# SCH_RGS-Turret_2023-06-20.net
KiCad netlist of a schematic drawn in EasyEDA
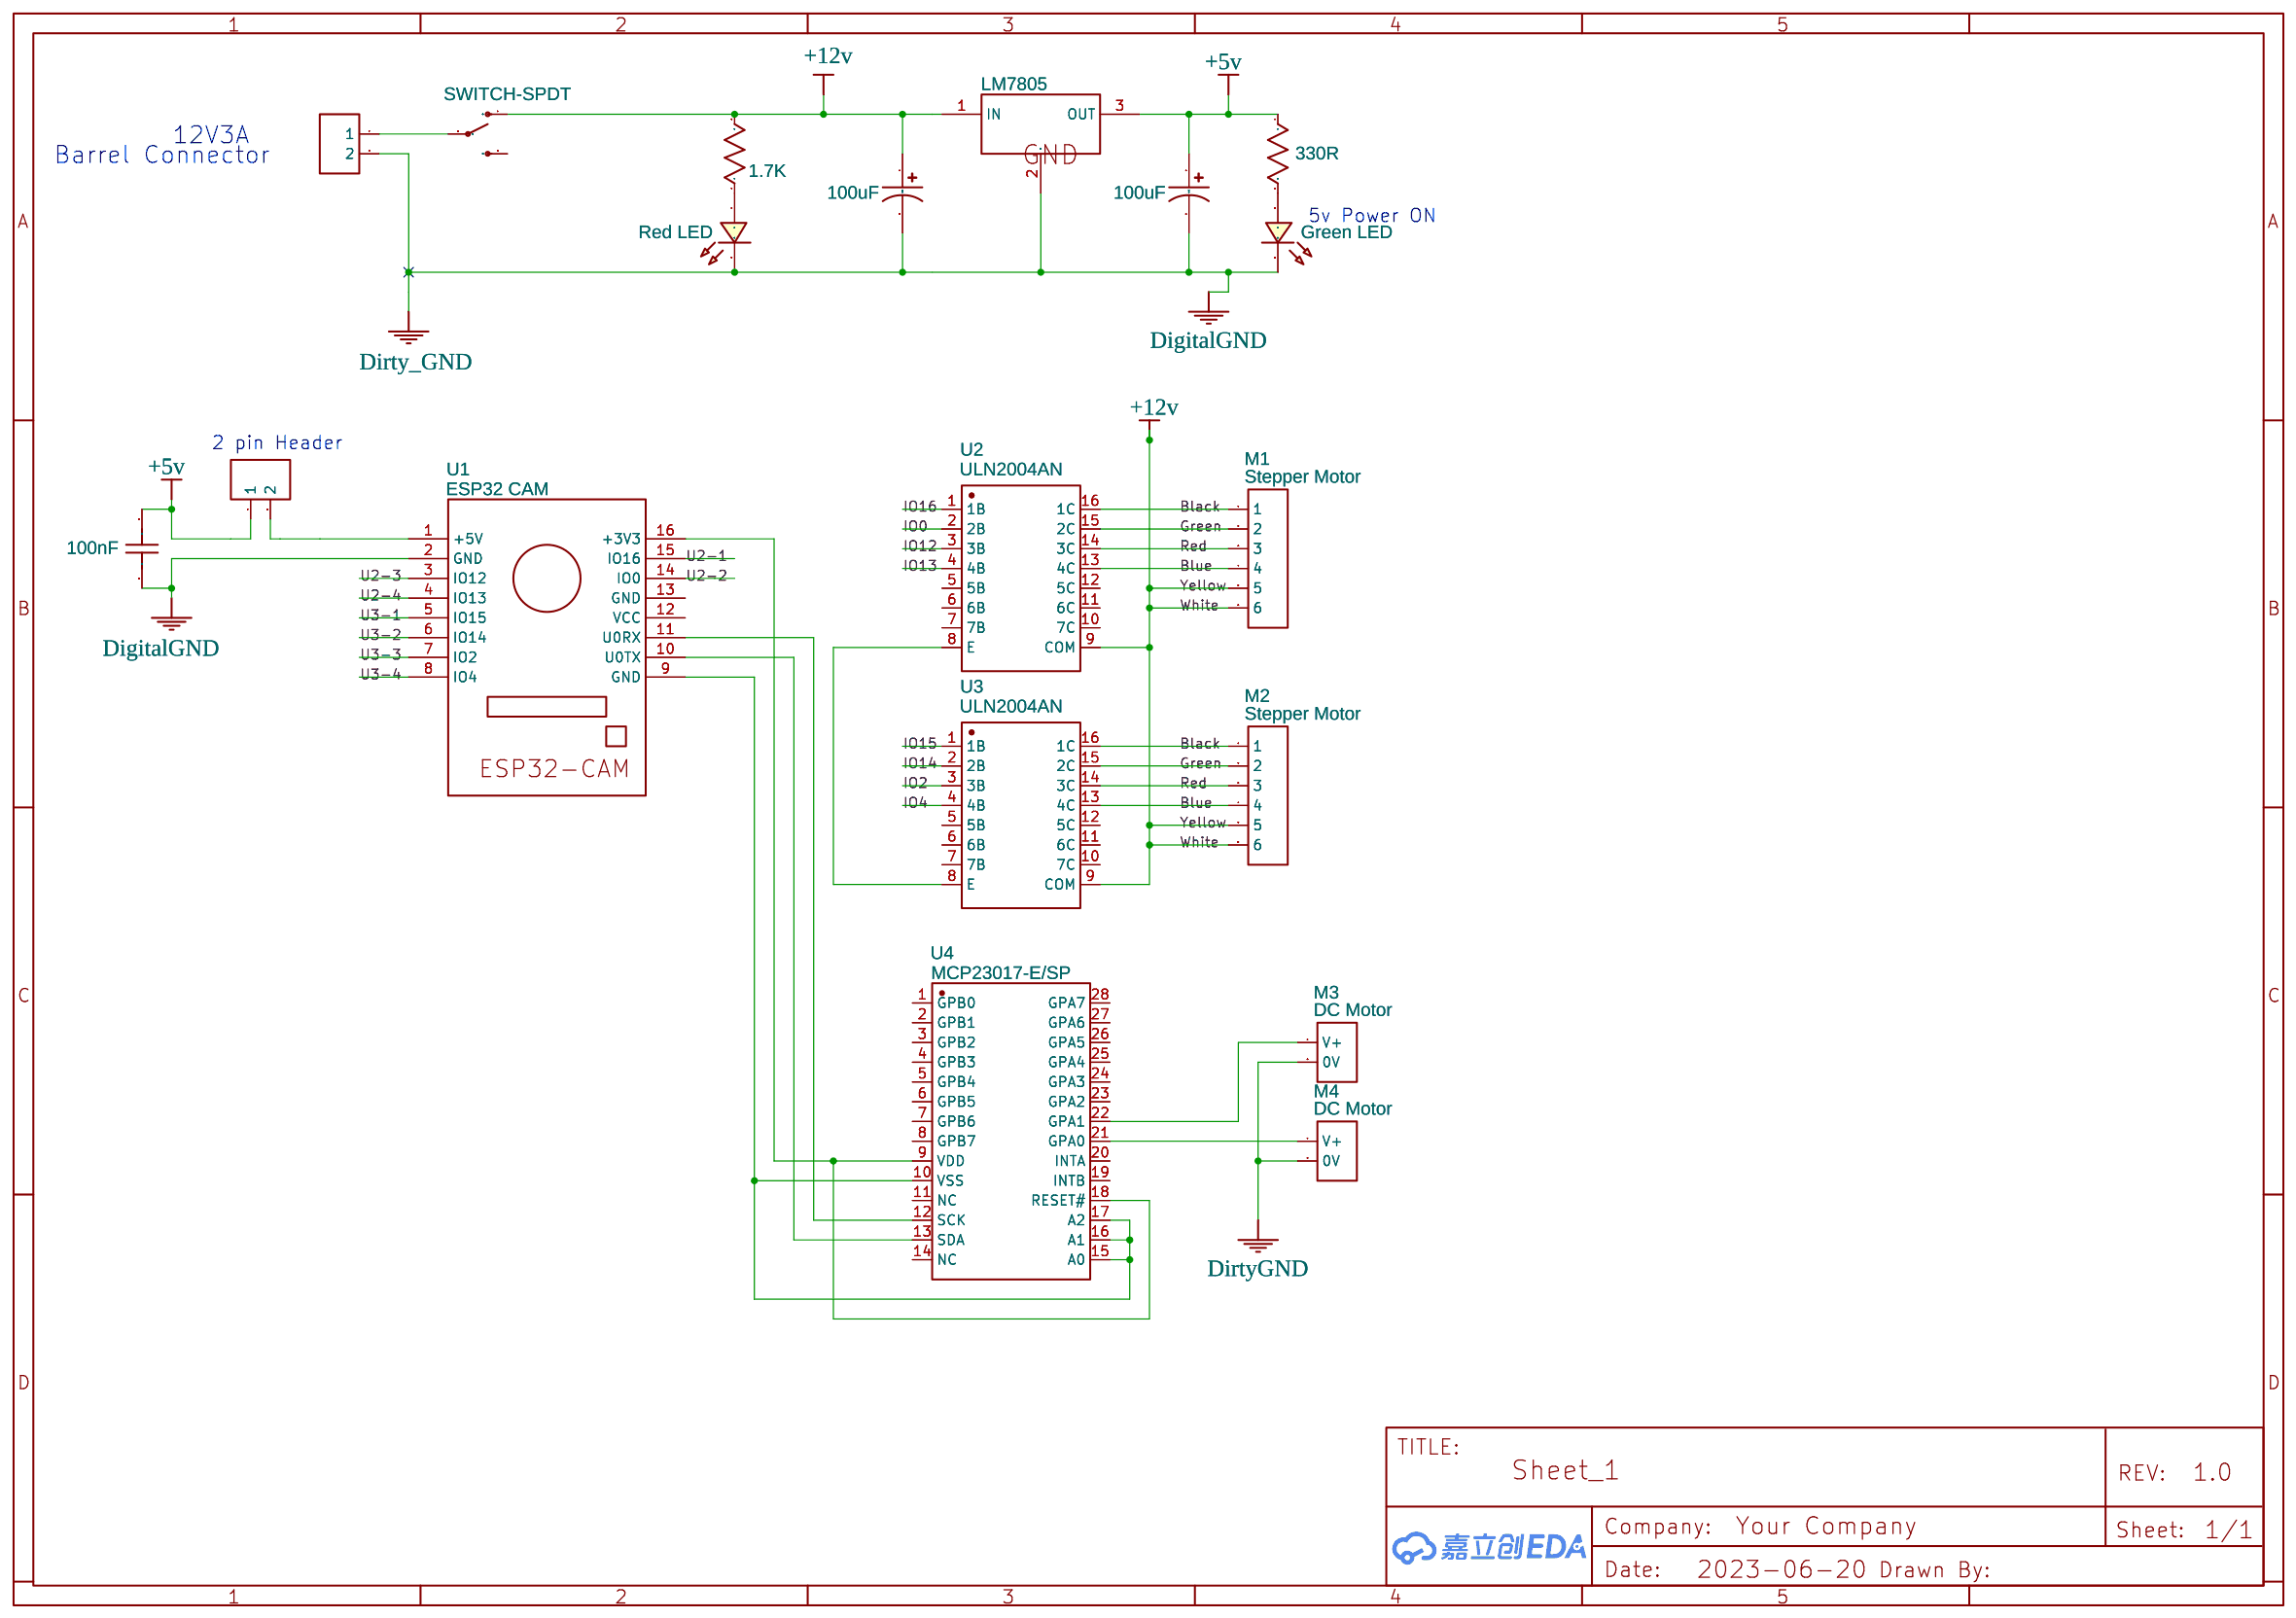
[diagram p0: schematic sheet]

(export (version "E")
  (design (tool "Eeschema 10.0.6"))
  (components
    (comp (ref "C1") (value "100uF") (libsource (lib "") (part "C_Tan_SMD_A_US")))
    (comp (ref "C2") (value "100uF") (libsource (lib "") (part "C_Tan_SMD_A_US")))
    (comp (ref "C3") (value "100nF") (libsource (lib "") (part "C_0603_US")))
    (comp (ref "H1")
      (value "HDR-F-2.54_1x2")
      (fields (field (name "BOM_Supplier Part") "C49661"))
      (libsource (lib "") (part "HDR-F-2.54_1x2_2"))
    )
    (comp (ref "H2")
      (value "HDR-F-2.54_1x2")
      (fields (field (name "BOM_Supplier Part") "C49661"))
      (libsource (lib "") (part "HDR-F-2.54_1x2"))
    )
    (comp (ref "LED1")
      (value "Red LED")
      (fields
        (field (name "BOM_Manufacturer Part") "19-217/R6C-AL1M2VY/3T")
        (field (name "BOM_Supplier Part") "C72044")
      )
      (libsource (lib "") (part "LED-0603_R"))
    )
    (comp (ref "LED2")
      (value "Green LED")
      (fields
        (field (name "BOM_Manufacturer Part") "19-217/R6C-AL1M2VY/3T")
        (field (name "BOM_Supplier Part") "C72044")
      )
      (libsource (lib "") (part "LED-0603_R_1"))
    )
    (comp (ref "M1")
      (value "Stepper Motor")
      (fields (field (name "BOM_Supplier Part") "C40877"))
      (libsource (lib "") (part "HDR-F-2.54_1x6"))
    )
    (comp (ref "M2")
      (value "Stepper Motor")
      (fields (field (name "BOM_Supplier Part") "C40877"))
      (libsource (lib "") (part "HDR-F-2.54_1x6"))
    )
    (comp (ref "M3")
      (value "DC Motor")
      (fields (field (name "BOM_Supplier Part") "C49661"))
      (libsource (lib "") (part "HDR-F-2.54_1x2_1"))
    )
    (comp (ref "M4")
      (value "DC Motor")
      (fields (field (name "BOM_Supplier Part") "C49661"))
      (libsource (lib "") (part "HDR-F-2.54_1x2_1"))
    )
    (comp (ref "R1") (value "330R") (libsource (lib "") (part "R_0603_US")))
    (comp (ref "R2") (value "1.7K") (libsource (lib "") (part "R_0603_US_1")))
    (comp (ref "S1") (value "SWITCH-SPDT") (libsource (lib "") (part "SWITCH-SPDT")))
    (comp (ref "U1") (value "ESP32 CAM") (libsource (lib "") (part "ESP32 CAM")))
    (comp (ref "U2")
      (value "ULN2004AN")
      (fields (field (name "BOM_Supplier Part") "C17226"))
      (libsource (lib "") (part "ULN2004AN"))
    )
    (comp (ref "U3")
      (value "ULN2004AN")
      (fields (field (name "BOM_Supplier Part") "C17226"))
      (libsource (lib "") (part "ULN2004AN"))
    )
    (comp (ref "U4")
      (value "MCP23017-E/SP")
      (fields (field (name "BOM_Supplier Part") "C647352"))
      (libsource (lib "") (part "MCP23017-E/SP"))
    )
    (comp (ref "U5")
      (value "LM7805")
      (fields (field (name "BOM_Manufacturer Part") "L7805CV-DG") (field (name "BOM_Supplier Part") "C3795"))
      (libsource (lib "") (part "L7805CV-DG"))
    )
  )
  (nets
    (net (code "1") (name "+5v") (class "Default")
      (node (ref "C1") (pin "1") (pinfunction "1_1") (pintype "unspecified"))
      (node (ref "C3") (pin "1") (pinfunction "1_1") (pintype "unspecified"))
      (node (ref "H2") (pin "1") (pinfunction "1_1") (pintype "input"))
      (node (ref "R1") (pin "1") (pinfunction "1_1") (pintype "unspecified"))
      (node (ref "U5") (pin "3") (pinfunction "OUT_3") (pintype "passive"))
    )
    (net (code "2") (name "+12v") (class "Default")
      (node (ref "C2") (pin "1") (pinfunction "1_1") (pintype "unspecified"))
      (node (ref "M1") (pin "5") (pinfunction "5_5") (pintype "input"))
      (node (ref "M1") (pin "6") (pinfunction "6_6") (pintype "input"))
      (node (ref "M2") (pin "5") (pinfunction "5_5") (pintype "input"))
      (node (ref "M2") (pin "6") (pinfunction "6_6") (pintype "input"))
      (node (ref "R2") (pin "2") (pinfunction "2_2") (pintype "unspecified"))
      (node (ref "S1") (pin "1") (pinfunction "O_1") (pintype "unspecified"))
      (node (ref "U2") (pin "9") (pinfunction "COM_9") (pintype "unspecified"))
      (node (ref "U3") (pin "9") (pinfunction "COM_9") (pintype "unspecified"))
      (node (ref "U5") (pin "1") (pinfunction "IN_1") (pintype "passive"))
    )
    (net (code "3") (name "/Black") (class "Default")
      (node (ref "M1") (pin "1") (pinfunction "1_1") (pintype "input"))
      (node (ref "M2") (pin "1") (pinfunction "1_1") (pintype "input"))
      (node (ref "U2") (pin "16") (pinfunction "1C_16") (pintype "unspecified"))
      (node (ref "U3") (pin "16") (pinfunction "1C_16") (pintype "unspecified"))
    )
    (net (code "4") (name "/Blue") (class "Default")
      (node (ref "M1") (pin "4") (pinfunction "4_4") (pintype "input"))
      (node (ref "M2") (pin "4") (pinfunction "4_4") (pintype "input"))
      (node (ref "U2") (pin "13") (pinfunction "4C_13") (pintype "unspecified"))
      (node (ref "U3") (pin "13") (pinfunction "4C_13") (pintype "unspecified"))
    )
    (net (code "5") (name "/Green") (class "Default")
      (node (ref "M1") (pin "2") (pinfunction "2_2") (pintype "input"))
      (node (ref "M2") (pin "2") (pinfunction "2_2") (pintype "input"))
      (node (ref "U2") (pin "15") (pinfunction "2C_15") (pintype "unspecified"))
      (node (ref "U3") (pin "15") (pinfunction "2C_15") (pintype "unspecified"))
    )
    (net (code "6") (name "/IO0") (class "Default")
      (node (ref "U2") (pin "2") (pinfunction "2B_2") (pintype "unspecified"))
    )
    (net (code "7") (name "/IO2") (class "Default")
      (node (ref "U3") (pin "3") (pinfunction "3B_3") (pintype "unspecified"))
    )
    (net (code "8") (name "/IO4") (class "Default")
      (node (ref "U3") (pin "4") (pinfunction "4B_4") (pintype "unspecified"))
    )
    (net (code "9") (name "/IO12") (class "Default")
      (node (ref "U2") (pin "3") (pinfunction "3B_3") (pintype "unspecified"))
    )
    (net (code "10") (name "/IO13") (class "Default")
      (node (ref "U2") (pin "4") (pinfunction "4B_4") (pintype "unspecified"))
    )
    (net (code "11") (name "/IO14") (class "Default")
      (node (ref "U3") (pin "2") (pinfunction "2B_2") (pintype "unspecified"))
    )
    (net (code "12") (name "/IO15") (class "Default")
      (node (ref "U3") (pin "1") (pinfunction "1B_1") (pintype "unspecified"))
    )
    (net (code "13") (name "/IO16") (class "Default")
      (node (ref "U2") (pin "1") (pinfunction "1B_1") (pintype "unspecified"))
    )
    (net (code "14") (name "/Red") (class "Default")
      (node (ref "M1") (pin "3") (pinfunction "3_3") (pintype "input"))
      (node (ref "M2") (pin "3") (pinfunction "3_3") (pintype "input"))
      (node (ref "U2") (pin "14") (pinfunction "3C_14") (pintype "unspecified"))
      (node (ref "U3") (pin "14") (pinfunction "3C_14") (pintype "unspecified"))
    )
    (net (code "15") (name "/U2-1") (class "Default")
      (node (ref "U1") (pin "15") (pinfunction "IO16_15") (pintype "unspecified"))
    )
    (net (code "16") (name "/U2-2") (class "Default")
      (node (ref "U1") (pin "14") (pinfunction "IO0_14") (pintype "unspecified"))
    )
    (net (code "17") (name "/U2-3") (class "Default")
      (node (ref "U1") (pin "3") (pinfunction "IO12_3") (pintype "unspecified"))
    )
    (net (code "18") (name "/U2-4") (class "Default")
      (node (ref "U1") (pin "4") (pinfunction "IO13_4") (pintype "unspecified"))
    )
    (net (code "19") (name "/U3-1") (class "Default")
      (node (ref "U1") (pin "5") (pinfunction "IO15_5") (pintype "unspecified"))
    )
    (net (code "20") (name "/U3-2") (class "Default")
      (node (ref "U1") (pin "6") (pinfunction "IO14_6") (pintype "unspecified"))
    )
    (net (code "21") (name "/U3-3") (class "Default")
      (node (ref "U1") (pin "7") (pinfunction "IO2_7") (pintype "unspecified"))
    )
    (net (code "22") (name "/U3-4") (class "Default")
      (node (ref "U1") (pin "8") (pinfunction "IO4_8") (pintype "unspecified"))
    )
    (net (code "23") (name "DigitalGND") (class "Default")
      (node (ref "C1") (pin "2") (pinfunction "2_2") (pintype "unspecified"))
      (node (ref "C2") (pin "2") (pinfunction "2_2") (pintype "unspecified"))
      (node (ref "C3") (pin "2") (pinfunction "2_2") (pintype "unspecified"))
      (node (ref "H1") (pin "2") (pinfunction "2_2") (pintype "input"))
      (node (ref "LED1") (pin "2") (pinfunction "2_2") (pintype "unspecified"))
      (node (ref "LED2") (pin "2") (pinfunction "2_2") (pintype "unspecified"))
      (node (ref "U1") (pin "2") (pinfunction "GND_2") (pintype "unspecified"))
      (node (ref "U5") (pin "2") (pinfunction "GND_2") (pintype "passive"))
    )
    (net (code "24") (name "DirtyGND") (class "Default")
      (node (ref "M3") (pin "2") (pinfunction "0V_2") (pintype "input"))
      (node (ref "M4") (pin "2") (pinfunction "0V_2") (pintype "input"))
    )
    (net (code "25") (name "Net-(LED1-Pad1)") (class "Default")
      (node (ref "LED1") (pin "1") (pinfunction "1_1") (pintype "unspecified"))
      (node (ref "R2") (pin "1") (pinfunction "1_1") (pintype "unspecified"))
    )
    (net (code "26") (name "Net-(LED2-Pad1)") (class "Default")
      (node (ref "LED2") (pin "1") (pinfunction "1_1") (pintype "unspecified"))
      (node (ref "R1") (pin "2") (pinfunction "2_2") (pintype "unspecified"))
    )
    (net (code "27") (name "Net-(M3-V+)") (class "Default")
      (node (ref "M3") (pin "1") (pinfunction "V+_1") (pintype "input"))
      (node (ref "U4") (pin "22") (pinfunction "GPA1_22") (pintype "unspecified"))
    )
    (net (code "28") (name "Net-(M4-V+)") (class "Default")
      (node (ref "M4") (pin "1") (pinfunction "V+_1") (pintype "input"))
      (node (ref "U4") (pin "21") (pinfunction "GPA0_21") (pintype "unspecified"))
    )
    (net (code "29") (name "Net-(S1-P)") (class "Default")
      (node (ref "H1") (pin "1") (pinfunction "1_1") (pintype "input"))
      (node (ref "S1") (pin "2") (pinfunction "P_2") (pintype "unspecified"))
    )
    (net (code "30") (name "Net-(U1-+3V3)") (class "Default")
      (node (ref "U1") (pin "16") (pinfunction "+3V3_16") (pintype "unspecified"))
      (node (ref "U4") (pin "18") (pinfunction "RESET#_18") (pintype "unspecified"))
      (node (ref "U4") (pin "9") (pinfunction "VDD_9") (pintype "unspecified"))
    )
    (net (code "31") (name "Net-(U1-+5V)") (class "Default")
      (node (ref "H2") (pin "2") (pinfunction "2_2") (pintype "input"))
      (node (ref "U1") (pin "1") (pinfunction "+5V_1") (pintype "unspecified"))
    )
    (net (code "32") (name "Net-(U1-U0RX)") (class "Default")
      (node (ref "U1") (pin "11") (pinfunction "U0RX_11") (pintype "unspecified"))
      (node (ref "U4") (pin "12") (pinfunction "SCK_12") (pintype "unspecified"))
    )
    (net (code "33") (name "Net-(U1-U0TX)") (class "Default")
      (node (ref "U1") (pin "10") (pinfunction "U0TX_10") (pintype "unspecified"))
      (node (ref "U4") (pin "13") (pinfunction "SDA_13") (pintype "unspecified"))
    )
    (net (code "34") (name "Net-(U2-E)") (class "Default")
      (node (ref "U2") (pin "8") (pinfunction "E_8") (pintype "unspecified"))
      (node (ref "U3") (pin "8") (pinfunction "E_8") (pintype "unspecified"))
    )
    (net (code "35") (name "Net-(U4-A0)") (class "Default")
      (node (ref "U1") (pin "9") (pinfunction "GND_9") (pintype "unspecified"))
      (node (ref "U4") (pin "10") (pinfunction "VSS_10") (pintype "unspecified"))
      (node (ref "U4") (pin "15") (pinfunction "A0_15") (pintype "unspecified"))
      (node (ref "U4") (pin "16") (pinfunction "A1_16") (pintype "unspecified"))
      (node (ref "U4") (pin "17") (pinfunction "A2_17") (pintype "unspecified"))
    )
    (net (code "36") (name "unconnected-(S1-S-Pad3)") (class "Default")
      (node (ref "S1") (pin "3") (pinfunction "S_3") (pintype "unspecified"))
    )
    (net (code "37") (name "unconnected-(U1-GND-Pad13)") (class "Default")
      (node (ref "U1") (pin "13") (pinfunction "GND_13") (pintype "unspecified"))
    )
    (net (code "38") (name "unconnected-(U1-VCC-Pad12)") (class "Default")
      (node (ref "U1") (pin "12") (pinfunction "VCC_12") (pintype "unspecified"))
    )
    (net (code "39") (name "unconnected-(U2-5B-Pad5)") (class "Default")
      (node (ref "U2") (pin "5") (pinfunction "5B_5") (pintype "unspecified"))
    )
    (net (code "40") (name "unconnected-(U2-5C-Pad12)") (class "Default")
      (node (ref "U2") (pin "12") (pinfunction "5C_12") (pintype "unspecified"))
    )
    (net (code "41") (name "unconnected-(U2-6B-Pad6)") (class "Default")
      (node (ref "U2") (pin "6") (pinfunction "6B_6") (pintype "unspecified"))
    )
    (net (code "42") (name "unconnected-(U2-6C-Pad11)") (class "Default")
      (node (ref "U2") (pin "11") (pinfunction "6C_11") (pintype "unspecified"))
    )
    (net (code "43") (name "unconnected-(U2-7B-Pad7)") (class "Default")
      (node (ref "U2") (pin "7") (pinfunction "7B_7") (pintype "unspecified"))
    )
    (net (code "44") (name "unconnected-(U2-7C-Pad10)") (class "Default")
      (node (ref "U2") (pin "10") (pinfunction "7C_10") (pintype "unspecified"))
    )
    (net (code "45") (name "unconnected-(U3-5B-Pad5)") (class "Default")
      (node (ref "U3") (pin "5") (pinfunction "5B_5") (pintype "unspecified"))
    )
    (net (code "46") (name "unconnected-(U3-5C-Pad12)") (class "Default")
      (node (ref "U3") (pin "12") (pinfunction "5C_12") (pintype "unspecified"))
    )
    (net (code "47") (name "unconnected-(U3-6B-Pad6)") (class "Default")
      (node (ref "U3") (pin "6") (pinfunction "6B_6") (pintype "unspecified"))
    )
    (net (code "48") (name "unconnected-(U3-6C-Pad11)") (class "Default")
      (node (ref "U3") (pin "11") (pinfunction "6C_11") (pintype "unspecified"))
    )
    (net (code "49") (name "unconnected-(U3-7B-Pad7)") (class "Default")
      (node (ref "U3") (pin "7") (pinfunction "7B_7") (pintype "unspecified"))
    )
    (net (code "50") (name "unconnected-(U3-7C-Pad10)") (class "Default")
      (node (ref "U3") (pin "10") (pinfunction "7C_10") (pintype "unspecified"))
    )
    (net (code "51") (name "unconnected-(U4-GPA2-Pad23)") (class "Default")
      (node (ref "U4") (pin "23") (pinfunction "GPA2_23") (pintype "unspecified"))
    )
    (net (code "52") (name "unconnected-(U4-GPA3-Pad24)") (class "Default")
      (node (ref "U4") (pin "24") (pinfunction "GPA3_24") (pintype "unspecified"))
    )
    (net (code "53") (name "unconnected-(U4-GPA4-Pad25)") (class "Default")
      (node (ref "U4") (pin "25") (pinfunction "GPA4_25") (pintype "unspecified"))
    )
    (net (code "54") (name "unconnected-(U4-GPA5-Pad26)") (class "Default")
      (node (ref "U4") (pin "26") (pinfunction "GPA5_26") (pintype "unspecified"))
    )
    (net (code "55") (name "unconnected-(U4-GPA6-Pad27)") (class "Default")
      (node (ref "U4") (pin "27") (pinfunction "GPA6_27") (pintype "unspecified"))
    )
    (net (code "56") (name "unconnected-(U4-GPA7-Pad28)") (class "Default")
      (node (ref "U4") (pin "28") (pinfunction "GPA7_28") (pintype "unspecified"))
    )
    (net (code "57") (name "unconnected-(U4-GPB0-Pad1)") (class "Default")
      (node (ref "U4") (pin "1") (pinfunction "GPB0_1") (pintype "unspecified"))
    )
    (net (code "58") (name "unconnected-(U4-GPB1-Pad2)") (class "Default")
      (node (ref "U4") (pin "2") (pinfunction "GPB1_2") (pintype "unspecified"))
    )
    (net (code "59") (name "unconnected-(U4-GPB2-Pad3)") (class "Default")
      (node (ref "U4") (pin "3") (pinfunction "GPB2_3") (pintype "unspecified"))
    )
    (net (code "60") (name "unconnected-(U4-GPB3-Pad4)") (class "Default")
      (node (ref "U4") (pin "4") (pinfunction "GPB3_4") (pintype "unspecified"))
    )
    (net (code "61") (name "unconnected-(U4-GPB4-Pad5)") (class "Default")
      (node (ref "U4") (pin "5") (pinfunction "GPB4_5") (pintype "unspecified"))
    )
    (net (code "62") (name "unconnected-(U4-GPB5-Pad6)") (class "Default")
      (node (ref "U4") (pin "6") (pinfunction "GPB5_6") (pintype "unspecified"))
    )
    (net (code "63") (name "unconnected-(U4-GPB6-Pad7)") (class "Default")
      (node (ref "U4") (pin "7") (pinfunction "GPB6_7") (pintype "unspecified"))
    )
    (net (code "64") (name "unconnected-(U4-GPB7-Pad8)") (class "Default")
      (node (ref "U4") (pin "8") (pinfunction "GPB7_8") (pintype "unspecified"))
    )
    (net (code "65") (name "unconnected-(U4-INTA-Pad20)") (class "Default")
      (node (ref "U4") (pin "20") (pinfunction "INTA_20") (pintype "unspecified"))
    )
    (net (code "66") (name "unconnected-(U4-INTB-Pad19)") (class "Default")
      (node (ref "U4") (pin "19") (pinfunction "INTB_19") (pintype "unspecified"))
    )
    (net (code "67") (name "unconnected-(U4-NC-Pad11)") (class "Default")
      (node (ref "U4") (pin "11") (pinfunction "NC_11") (pintype "unspecified"))
    )
    (net (code "68") (name "unconnected-(U4-NC-Pad14)") (class "Default")
      (node (ref "U4") (pin "14") (pinfunction "NC_14") (pintype "unspecified"))
    )
  )
)
